# Cansat_2018_V2.net
KiCad netlist of a schematic drawn in EAGLE
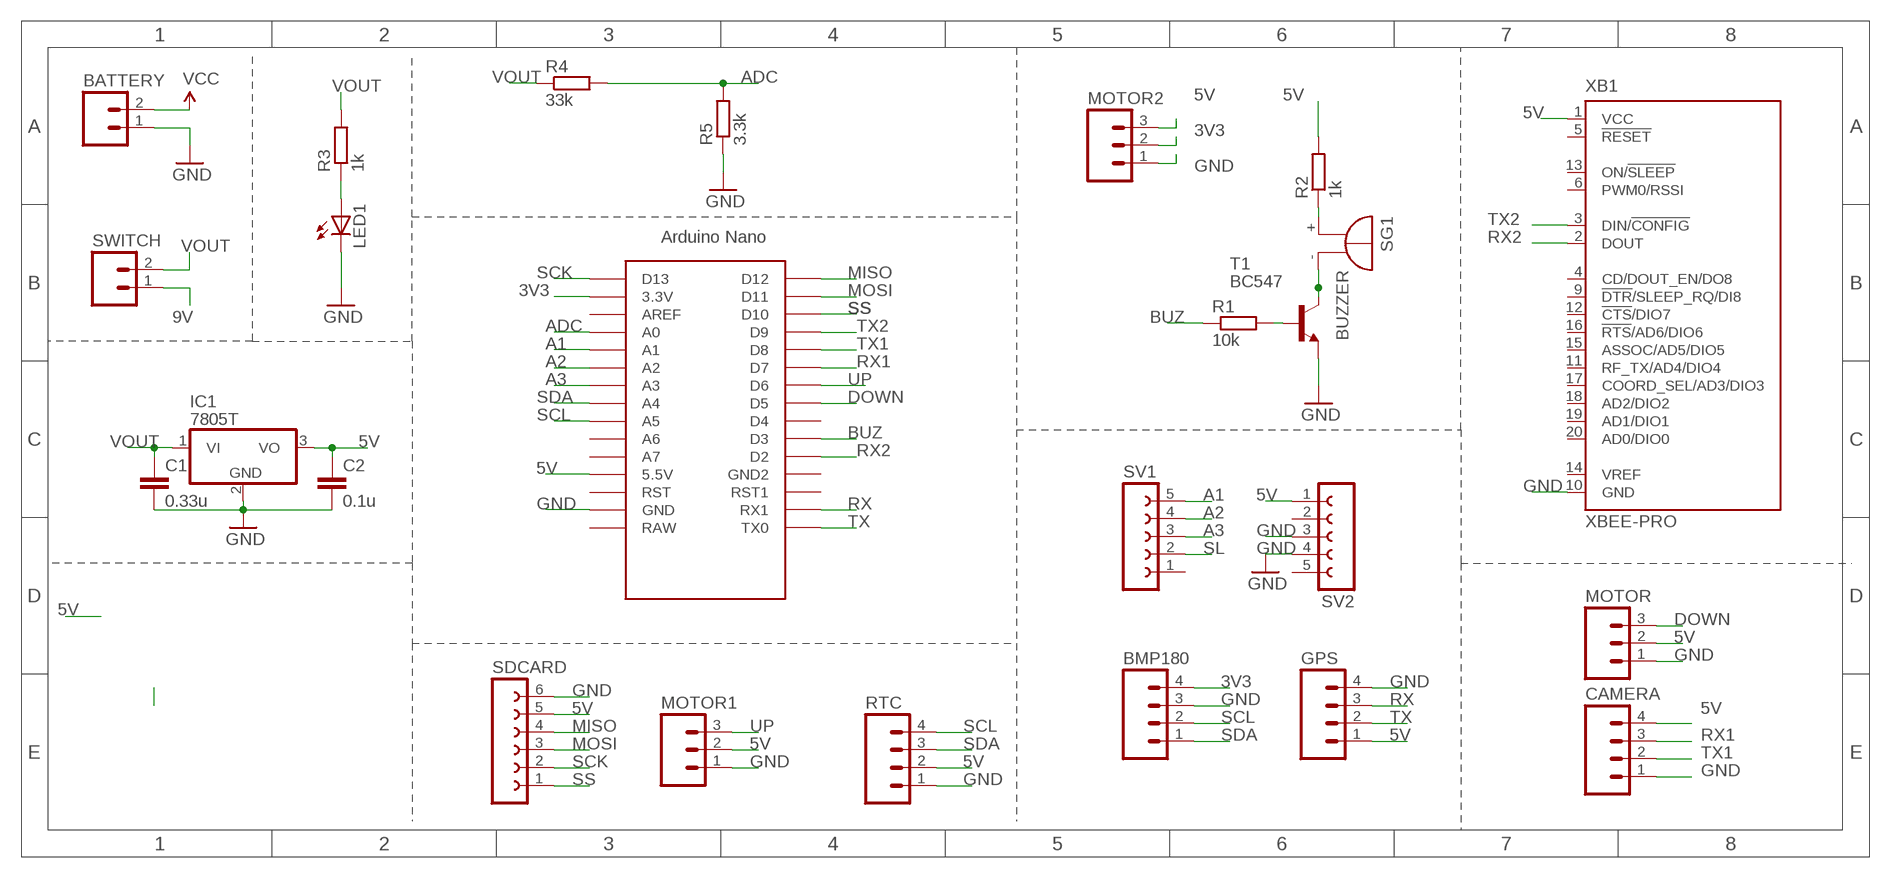
[diagram p0: schematic, sheet 1]

(export (version "E")
  (design (tool "Eeschema 10.0.6"))
  (components
    (comp (ref "BATTERY")
      (value "M02")
      (footprint "eagle-import:02P")
      (libsource (lib "eagle-import") (part "M02"))
    )
    (comp (ref "BMP180")
      (value "M04")
      (footprint "eagle-import:04P")
      (libsource (lib "eagle-import") (part "M04"))
    )
    (comp (ref "C1")
      (value "0.33u")
      (footprint "eagle-import:C0805")
      (libsource (lib "eagle-import") (part "rcl_C-EUC0805"))
    )
    (comp (ref "C2")
      (value "0.1u")
      (footprint "eagle-import:C0805")
      (libsource (lib "eagle-import") (part "C-EUC0805"))
    )
    (comp (ref "CAMERA")
      (value "M04")
      (footprint "eagle-import:04P")
      (libsource (lib "eagle-import") (part "M04"))
    )
    (comp (ref "GPS")
      (value "M04")
      (footprint "eagle-import:04P")
      (libsource (lib "eagle-import") (part "M04"))
    )
    (comp (ref "IC1")
      (value "7805T")
      (footprint "eagle-import:TO220H")
      (libsource (lib "eagle-import") (part "78T05"))
    )
    (comp (ref "LED1")
      (value "LED3MM")
      (footprint "eagle-import:LED3MM")
      (libsource (lib "eagle-import") (part "LED3MM"))
    )
    (comp (ref "MOTOR")
      (value "M03")
      (footprint "eagle-import:03P")
      (libsource (lib "eagle-import") (part "M03"))
    )
    (comp (ref "MOTOR1")
      (value "M03")
      (footprint "eagle-import:03P")
      (libsource (lib "eagle-import") (part "M03"))
    )
    (comp (ref "MOTOR2")
      (value "M03")
      (footprint "eagle-import:03P")
      (libsource (lib "eagle-import") (part "M03"))
    )
    (comp (ref "R1")
      (value "10k")
      (footprint "eagle-import:0207_7")
      (libsource (lib "eagle-import") (part "R-EU_0207/7"))
    )
    (comp (ref "R2")
      (value "1k")
      (footprint "eagle-import:0207_7")
      (libsource (lib "eagle-import") (part "R-EU_0207/7"))
    )
    (comp (ref "R3")
      (value "1k")
      (footprint "eagle-import:0204_7")
      (libsource (lib "eagle-import") (part "R-EU_0204/7"))
    )
    (comp (ref "R4")
      (value "33k")
      (footprint "eagle-import:0207_7")
      (libsource (lib "eagle-import") (part "R-EU_0207/7"))
    )
    (comp (ref "R5")
      (value "3.3k")
      (footprint "eagle-import:0207_10")
      (libsource (lib "eagle-import") (part "R0207/10"))
    )
    (comp (ref "RTC")
      (value "M04")
      (footprint "eagle-import:04P")
      (libsource (lib "eagle-import") (part "M04"))
    )
    (comp (ref "SDCARD")
      (value "FE06-1")
      (footprint "eagle-import:FE06")
      (libsource (lib "eagle-import") (part "FE06-1"))
    )
    (comp (ref "SG1")
      (value "BUZZER")
      (footprint "eagle-import:F_TMB")
      (libsource (lib "eagle-import") (part "BUZZER"))
    )
    (comp (ref "SV1")
      (value "FE05-1")
      (footprint "eagle-import:FE05-1")
      (libsource (lib "eagle-import") (part "FE05-1"))
    )
    (comp (ref "SV2")
      (value "FE05-1")
      (footprint "eagle-import:FE05-1")
      (libsource (lib "eagle-import") (part "FE05-1"))
    )
    (comp (ref "SWITCH")
      (value "M02")
      (footprint "eagle-import:02P")
      (libsource (lib "eagle-import") (part "M02"))
    )
    (comp (ref "T1")
      (value "BC547")
      (footprint "eagle-import:TO92")
      (libsource (lib "eagle-import") (part "BC547"))
    )
    (comp (ref "U$1")
      (value "NANO")
      (footprint "eagle-import:NANO")
      (libsource (lib "eagle-import") (part "NANO"))
    )
    (comp (ref "XB1")
      (value "XBEE-PRO")
      (footprint "eagle-import:XBEE-PRO")
      (fields (field (name "MPN") "XBP24-AWI-001"))
      (libsource (lib "eagle-import") (part "XBEE-PRO"))
    )
  )
  (nets
    (net (code "1") (name "/3V3") (class "Default")
      (node (ref "BMP180") (pin "4") (pinfunction "4_4") (pintype "passive"))
      (node (ref "MOTOR2") (pin "2") (pinfunction "2_2") (pintype "passive"))
      (node (ref "U$1") (pin "3.3V") (pinfunction "3.3V_3.3V") (pintype "bidirectional"))
    )
    (net (code "2") (name "/5V") (class "Default")
      (node (ref "C2") (pin "1") (pinfunction "1_1") (pintype "passive"))
      (node (ref "CAMERA") (pin "4") (pinfunction "4_4") (pintype "passive"))
      (node (ref "GPS") (pin "1") (pinfunction "1_1") (pintype "passive"))
      (node (ref "IC1") (pin "3") (pinfunction "VO_3") (pintype "passive"))
      (node (ref "MOTOR") (pin "2") (pinfunction "2_2") (pintype "passive"))
      (node (ref "MOTOR1") (pin "2") (pinfunction "2_2") (pintype "passive"))
      (node (ref "MOTOR2") (pin "3") (pinfunction "3_3") (pintype "passive"))
      (node (ref "R2") (pin "2") (pinfunction "2_2") (pintype "passive"))
      (node (ref "RTC") (pin "2") (pinfunction "2_2") (pintype "passive"))
      (node (ref "SDCARD") (pin "5") (pinfunction "5_5") (pintype "passive"))
      (node (ref "SV2") (pin "1") (pinfunction "1_1") (pintype "passive"))
      (node (ref "U$1") (pin "5V") (pinfunction "5.5V_5V") (pintype "bidirectional"))
      (node (ref "XB1") (pin "1") (pinfunction "VCC_1") (pintype "power_in"))
    )
    (net (code "3") (name "/A1") (class "Default")
      (node (ref "SV1") (pin "5") (pinfunction "5_5") (pintype "passive"))
      (node (ref "U$1") (pin "A1") (pinfunction "A1_A1") (pintype "bidirectional"))
    )
    (net (code "4") (name "/A2") (class "Default")
      (node (ref "SV1") (pin "4") (pinfunction "4_4") (pintype "passive"))
      (node (ref "U$1") (pin "A2") (pinfunction "A2_A2") (pintype "bidirectional"))
    )
    (net (code "5") (name "/A3") (class "Default")
      (node (ref "SV1") (pin "3") (pinfunction "3_3") (pintype "passive"))
      (node (ref "U$1") (pin "A3") (pinfunction "A3_A3") (pintype "bidirectional"))
    )
    (net (code "6") (name "/ADC") (class "Default")
      (node (ref "R4") (pin "2") (pinfunction "2_2") (pintype "passive"))
      (node (ref "R5") (pin "2") (pinfunction "2_2") (pintype "passive"))
      (node (ref "U$1") (pin "A0") (pinfunction "A0_A0") (pintype "bidirectional"))
    )
    (net (code "7") (name "/BUZ") (class "Default")
      (node (ref "R1") (pin "1") (pinfunction "1_1") (pintype "passive"))
      (node (ref "U$1") (pin "D3") (pinfunction "D3_D3") (pintype "bidirectional"))
    )
    (net (code "8") (name "/DOWN") (class "Default")
      (node (ref "MOTOR") (pin "3") (pinfunction "3_3") (pintype "passive"))
      (node (ref "U$1") (pin "D5") (pinfunction "D5_D5") (pintype "bidirectional"))
    )
    (net (code "9") (name "/MISO") (class "Default")
      (node (ref "SDCARD") (pin "4") (pinfunction "4_4") (pintype "passive"))
      (node (ref "U$1") (pin "D12") (pinfunction "D12_D12") (pintype "bidirectional"))
    )
    (net (code "10") (name "/MOSI") (class "Default")
      (node (ref "SDCARD") (pin "3") (pinfunction "3_3") (pintype "passive"))
      (node (ref "U$1") (pin "D11") (pinfunction "D11_D11") (pintype "bidirectional"))
    )
    (net (code "11") (name "/RX") (class "Default")
      (node (ref "GPS") (pin "3") (pinfunction "3_3") (pintype "passive"))
      (node (ref "U$1") (pin "RX1") (pinfunction "RX1_RX1") (pintype "bidirectional"))
    )
    (net (code "12") (name "/RX1") (class "Default")
      (node (ref "CAMERA") (pin "3") (pinfunction "3_3") (pintype "passive"))
      (node (ref "U$1") (pin "D7") (pinfunction "D7_D7") (pintype "bidirectional"))
    )
    (net (code "13") (name "/RX2") (class "Default")
      (node (ref "U$1") (pin "D2") (pinfunction "D2_D2") (pintype "bidirectional"))
      (node (ref "XB1") (pin "2") (pinfunction "DOUT_2") (pintype "output"))
    )
    (net (code "14") (name "/SCK") (class "Default")
      (node (ref "SDCARD") (pin "2") (pinfunction "2_2") (pintype "passive"))
      (node (ref "U$1") (pin "D13") (pinfunction "D13_D13") (pintype "bidirectional"))
    )
    (net (code "15") (name "/SCL") (class "Default")
      (node (ref "BMP180") (pin "2") (pinfunction "2_2") (pintype "passive"))
      (node (ref "RTC") (pin "4") (pinfunction "4_4") (pintype "passive"))
      (node (ref "U$1") (pin "A5") (pinfunction "A5_A5") (pintype "bidirectional"))
    )
    (net (code "16") (name "/SDA") (class "Default")
      (node (ref "BMP180") (pin "1") (pinfunction "1_1") (pintype "passive"))
      (node (ref "RTC") (pin "3") (pinfunction "3_3") (pintype "passive"))
      (node (ref "U$1") (pin "A4") (pinfunction "A4_A4") (pintype "bidirectional"))
    )
    (net (code "17") (name "/SL") (class "Default")
      (node (ref "SV1") (pin "2") (pinfunction "2_2") (pintype "passive"))
    )
    (net (code "18") (name "/SS") (class "Default")
      (node (ref "SDCARD") (pin "1") (pinfunction "1_1") (pintype "passive"))
      (node (ref "U$1") (pin "D10") (pinfunction "D10_D10") (pintype "bidirectional"))
    )
    (net (code "19") (name "/TX") (class "Default")
      (node (ref "GPS") (pin "2") (pinfunction "2_2") (pintype "passive"))
      (node (ref "U$1") (pin "TX0") (pinfunction "TX0_TX0") (pintype "bidirectional"))
    )
    (net (code "20") (name "/TX1") (class "Default")
      (node (ref "CAMERA") (pin "2") (pinfunction "2_2") (pintype "passive"))
      (node (ref "U$1") (pin "D8") (pinfunction "D8_D8") (pintype "bidirectional"))
    )
    (net (code "21") (name "/TX2") (class "Default")
      (node (ref "U$1") (pin "D9") (pinfunction "D9_D9") (pintype "bidirectional"))
      (node (ref "XB1") (pin "3") (pinfunction "DIN/~{CONFIG}_3") (pintype "input"))
    )
    (net (code "22") (name "/UP") (class "Default")
      (node (ref "MOTOR1") (pin "3") (pinfunction "3_3") (pintype "passive"))
      (node (ref "U$1") (pin "D6") (pinfunction "D6_D6") (pintype "bidirectional"))
    )
    (net (code "23") (name "/VOUT") (class "Default")
      (node (ref "C1") (pin "1") (pinfunction "1_1") (pintype "passive"))
      (node (ref "IC1") (pin "1") (pinfunction "VI_1") (pintype "input"))
      (node (ref "R3") (pin "2") (pinfunction "2_2") (pintype "passive"))
      (node (ref "R4") (pin "1") (pinfunction "1_1") (pintype "passive"))
      (node (ref "SWITCH") (pin "2") (pinfunction "2_2") (pintype "passive"))
    )
    (net (code "24") (name "GND") (class "Default")
      (node (ref "BATTERY") (pin "1") (pinfunction "1_1") (pintype "passive"))
      (node (ref "BMP180") (pin "3") (pinfunction "3_3") (pintype "passive"))
      (node (ref "C1") (pin "2") (pinfunction "2_2") (pintype "passive"))
      (node (ref "C2") (pin "2") (pinfunction "2_2") (pintype "passive"))
      (node (ref "CAMERA") (pin "1") (pinfunction "1_1") (pintype "passive"))
      (node (ref "GPS") (pin "4") (pinfunction "4_4") (pintype "passive"))
      (node (ref "IC1") (pin "2") (pinfunction "GND_2") (pintype "passive"))
      (node (ref "LED1") (pin "K") (pinfunction "C_K") (pintype "passive"))
      (node (ref "MOTOR") (pin "1") (pinfunction "1_1") (pintype "passive"))
      (node (ref "MOTOR1") (pin "1") (pinfunction "1_1") (pintype "passive"))
      (node (ref "MOTOR2") (pin "1") (pinfunction "1_1") (pintype "passive"))
      (node (ref "R5") (pin "1") (pinfunction "1_1") (pintype "passive"))
      (node (ref "RTC") (pin "1") (pinfunction "1_1") (pintype "passive"))
      (node (ref "SDCARD") (pin "6") (pinfunction "6_6") (pintype "passive"))
      (node (ref "SV2") (pin "3") (pinfunction "3_3") (pintype "passive"))
      (node (ref "SV2") (pin "4") (pinfunction "4_4") (pintype "passive"))
      (node (ref "T1") (pin "1") (pinfunction "E_1") (pintype "passive"))
      (node (ref "U$1") (pin "GND") (pinfunction "GND_GND") (pintype "bidirectional"))
      (node (ref "XB1") (pin "10") (pinfunction "GND_10") (pintype "power_in"))
    )
    (net (code "25") (name "Net-(LED1-PadA)") (class "Default")
      (node (ref "LED1") (pin "A") (pinfunction "A_A") (pintype "passive"))
      (node (ref "R3") (pin "1") (pinfunction "1_1") (pintype "passive"))
    )
    (net (code "26") (name "Net-(R2-Pad1)") (class "Default")
      (node (ref "R2") (pin "1") (pinfunction "1_1") (pintype "passive"))
      (node (ref "SG1") (pin "+") (pinfunction "+_+") (pintype "passive"))
    )
    (net (code "27") (name "Net-(T1-B)") (class "Default")
      (node (ref "R1") (pin "2") (pinfunction "2_2") (pintype "passive"))
      (node (ref "T1") (pin "2") (pinfunction "B_2") (pintype "passive"))
    )
    (net (code "28") (name "Net-(T1-C)") (class "Default")
      (node (ref "SG1") (pin "-") (pinfunction "-_-") (pintype "passive"))
      (node (ref "T1") (pin "3") (pinfunction "C_3") (pintype "passive"))
    )
    (net (code "29") (name "VCC") (class "Default")
      (node (ref "BATTERY") (pin "2") (pinfunction "2_2") (pintype "passive"))
      (node (ref "SWITCH") (pin "1") (pinfunction "1_1") (pintype "passive"))
    )
    (net (code "30") (name "unconnected-(SV1-Pad1)") (class "Default")
      (node (ref "SV1") (pin "1") (pinfunction "1_1") (pintype "passive"))
    )
    (net (code "31") (name "unconnected-(SV2-Pad2)") (class "Default")
      (node (ref "SV2") (pin "2") (pinfunction "2_2") (pintype "passive"))
    )
    (net (code "32") (name "unconnected-(SV2-Pad5)") (class "Default")
      (node (ref "SV2") (pin "5") (pinfunction "5_5") (pintype "passive"))
    )
    (net (code "33") (name "unconnected-(U$1-GND2-PadGND1)") (class "Default")
      (node (ref "U$1") (pin "GND1") (pinfunction "GND2_GND1") (pintype "bidirectional"))
    )
    (net (code "34") (name "unconnected-(U$1-PadA6)") (class "Default")
      (node (ref "U$1") (pin "A6") (pinfunction "A6_A6") (pintype "bidirectional"))
    )
    (net (code "35") (name "unconnected-(U$1-PadA7)") (class "Default")
      (node (ref "U$1") (pin "A7") (pinfunction "A7_A7") (pintype "bidirectional"))
    )
    (net (code "36") (name "unconnected-(U$1-PadAREF)") (class "Default")
      (node (ref "U$1") (pin "AREF") (pinfunction "AREF_AREF") (pintype "bidirectional"))
    )
    (net (code "37") (name "unconnected-(U$1-PadD4)") (class "Default")
      (node (ref "U$1") (pin "D4") (pinfunction "D4_D4") (pintype "bidirectional"))
    )
    (net (code "38") (name "unconnected-(U$1-PadICSP1)") (class "Default")
      (node (ref "U$1") (pin "ICSP1") (pinfunction "ICSP1_ICSP1") (pintype "bidirectional"))
    )
    (net (code "39") (name "unconnected-(U$1-PadICSP2)") (class "Default")
      (node (ref "U$1") (pin "ICSP2") (pinfunction "ICSP2_ICSP2") (pintype "bidirectional"))
    )
    (net (code "40") (name "unconnected-(U$1-PadICSP3)") (class "Default")
      (node (ref "U$1") (pin "ICSP3") (pinfunction "ICSP3_ICSP3") (pintype "bidirectional"))
    )
    (net (code "41") (name "unconnected-(U$1-PadICSP4)") (class "Default")
      (node (ref "U$1") (pin "ICSP4") (pinfunction "ICSP4_ICSP4") (pintype "bidirectional"))
    )
    (net (code "42") (name "unconnected-(U$1-PadICSP5)") (class "Default")
      (node (ref "U$1") (pin "ICSP5") (pinfunction "ICSP5_ICSP5") (pintype "bidirectional"))
    )
    (net (code "43") (name "unconnected-(U$1-PadICSP6)") (class "Default")
      (node (ref "U$1") (pin "ICSP6") (pinfunction "ICSP6_ICSP6") (pintype "bidirectional"))
    )
    (net (code "44") (name "unconnected-(U$1-PadRAW)") (class "Default")
      (node (ref "U$1") (pin "RAW") (pinfunction "RAW_RAW") (pintype "bidirectional"))
    )
    (net (code "45") (name "unconnected-(U$1-PadRST)") (class "Default")
      (node (ref "U$1") (pin "RST") (pinfunction "RST_RST") (pintype "bidirectional"))
    )
    (net (code "46") (name "unconnected-(U$1-PadRST1)") (class "Default")
      (node (ref "U$1") (pin "RST1") (pinfunction "RST1_RST1") (pintype "bidirectional"))
    )
    (net (code "47") (name "unconnected-(XB1-AD0{slash}DIO0-Pad20)") (class "Default")
      (node (ref "XB1") (pin "20") (pinfunction "AD0/DIO0_20") (pintype "bidirectional"))
    )
    (net (code "48") (name "unconnected-(XB1-AD1{slash}DIO1-Pad19)") (class "Default")
      (node (ref "XB1") (pin "19") (pinfunction "AD1/DIO1_19") (pintype "bidirectional"))
    )
    (net (code "49") (name "unconnected-(XB1-AD2{slash}DIO2-Pad18)") (class "Default")
      (node (ref "XB1") (pin "18") (pinfunction "AD2/DIO2_18") (pintype "bidirectional"))
    )
    (net (code "50") (name "unconnected-(XB1-ASSOC{slash}AD5{slash}DIO5-Pad15)") (class "Default")
      (node (ref "XB1") (pin "15") (pinfunction "ASSOC/AD5/DIO5_15") (pintype "bidirectional"))
    )
    (net (code "51") (name "unconnected-(XB1-CD{slash}DOUT_EN{slash}DO8-Pad4)") (class "Default")
      (node (ref "XB1") (pin "4") (pinfunction "CD/DOUT_EN/DO8_4") (pintype "output"))
    )
    (net (code "52") (name "unconnected-(XB1-COORD_SEL{slash}AD3{slash}DIO3-Pad17)") (class "Default")
      (node (ref "XB1") (pin "17") (pinfunction "COORD_SEL/AD3/DIO3_17") (pintype "bidirectional"))
    )
    (net (code "53") (name "unconnected-(XB1-ON{slash}~{SLEEP}-Pad13)") (class "Default")
      (node (ref "XB1") (pin "13") (pinfunction "ON/~{SLEEP}_13") (pintype "output"))
    )
    (net (code "54") (name "unconnected-(XB1-PWM0{slash}RSSI-Pad6)") (class "Default")
      (node (ref "XB1") (pin "6") (pinfunction "PWM0/RSSI_6") (pintype "output"))
    )
    (net (code "55") (name "unconnected-(XB1-RF_TX{slash}AD4{slash}DIO4-Pad11)") (class "Default")
      (node (ref "XB1") (pin "11") (pinfunction "RF_TX/AD4/DIO4_11") (pintype "bidirectional"))
    )
    (net (code "56") (name "unconnected-(XB1-VREF-Pad14)") (class "Default")
      (node (ref "XB1") (pin "14") (pinfunction "VREF_14") (pintype "input"))
    )
    (net (code "57") (name "unconnected-(XB1-~{CTS}{slash}DIO7-Pad12)") (class "Default")
      (node (ref "XB1") (pin "12") (pinfunction "~{CTS}/DIO7_12") (pintype "bidirectional"))
    )
    (net (code "58") (name "unconnected-(XB1-~{DTR}{slash}SLEEP_RQ{slash}DI8-Pad9)") (class "Default")
      (node (ref "XB1") (pin "9") (pinfunction "~{DTR}/SLEEP_RQ/DI8_9") (pintype "bidirectional"))
    )
    (net (code "59") (name "unconnected-(XB1-~{RESET}-Pad5)") (class "Default")
      (node (ref "XB1") (pin "5") (pinfunction "~{RESET}_5") (pintype "input"))
    )
    (net (code "60") (name "unconnected-(XB1-~{RTS}{slash}AD6{slash}DIO6-Pad16)") (class "Default")
      (node (ref "XB1") (pin "16") (pinfunction "~{RTS}/AD6/DIO6_16") (pintype "bidirectional"))
    )
  )
)
